# 03_ESP32.net
KiCad netlist of a schematic drawn in Altium Designer
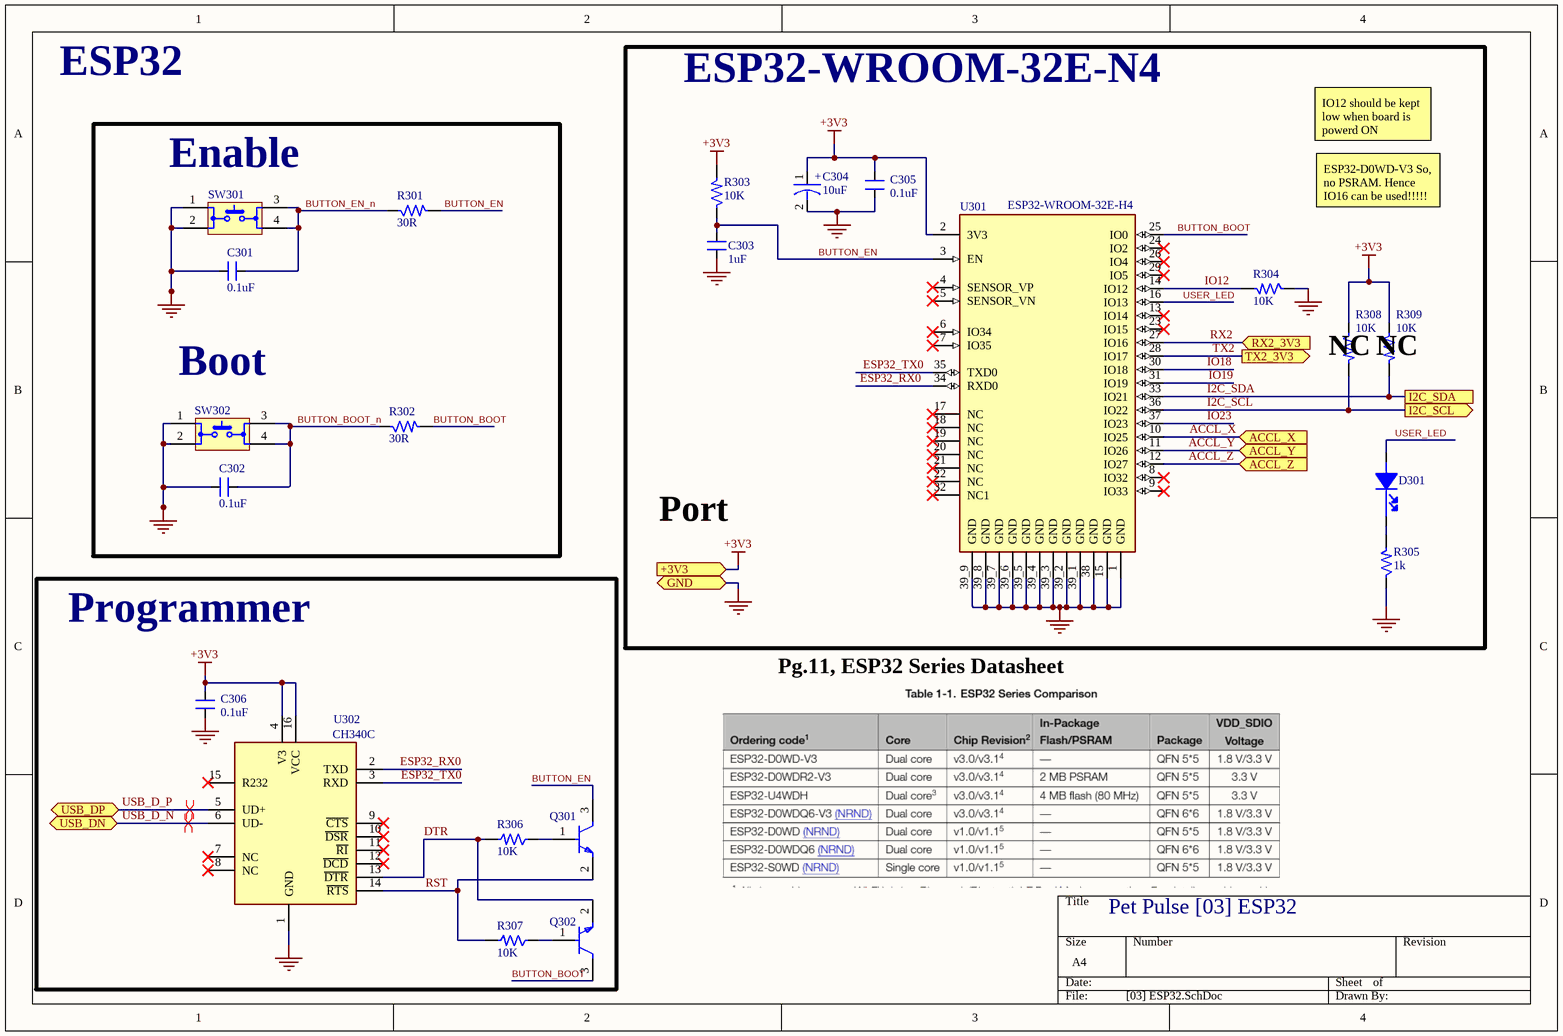
[diagram p0: [03] ESP32.SchDoc]

(export (version "E")
  (design (tool "Eeschema 10.0.6"))
  (components
    (comp (ref "C301")
      (value "0.1uF")
      (footprint "CAP_0805")
      (description "0.1µF ±10% 50V Ceramic Capacitor X7R 0805 (2012 Metric)")
      (fields
        (field (name "MANUFACTURER") "Samsung")
        (field (name "MANUFACTURER PART NUMBER") "CL21B104KBCNNNC")
      )
      (libsource (lib "IntegratedLibraryNamanTanwar") (part "CAP_0.1uF-50V-10%-0805"))
    )
    (comp (ref "C302")
      (value "0.1uF")
      (footprint "CAP_0805")
      (description "0.1µF ±10% 50V Ceramic Capacitor X7R 0805 (2012 Metric)")
      (fields
        (field (name "MANUFACTURER") "Samsung")
        (field (name "MANUFACTURER PART NUMBER") "CL21B104KBCNNNC")
      )
      (libsource (lib "IntegratedLibraryNamanTanwar") (part "CAP_0.1uF-50V-10%-0805"))
    )
    (comp (ref "C303")
      (value "1uF")
      (footprint "CAP_0805")
      (description "1µF ±5% 50V Ceramic Capacitor X7R 0805 (2012 Metric)")
      (fields
        (field (name "MANUFACTURER") "Samsung")
        (field (name "MANUFACTURER PART NUMBER") "CC0805JKX7R9BB105")
      )
      (libsource (lib "IntegratedLibraryNamanTanwar") (part "CAP_1uF-50V-5%-0805"))
    )
    (comp (ref "C304")
      (value "10uF")
      (footprint "CAP-T_1206")
      (description "10µF Molded Tantalum Capacitors 16V 1206 (3216 Metric) 3Ohm")
      (fields
        (field (name "MANUFACTURER") "AVX Corporation")
        (field (name "MANUFACTURER PART NUMBER") "TAJA106K016SNJ")
      )
      (libsource (lib "IntegratedLibraryNamanTanwar") (part "CAP-P_10uF-16V-10%-1206"))
    )
    (comp (ref "C305")
      (value "0.1uF")
      (footprint "CAP_0805")
      (description "0.1µF ±10% 50V Ceramic Capacitor X7R 0805 (2012 Metric)")
      (fields
        (field (name "MANUFACTURER") "Samsung")
        (field (name "MANUFACTURER PART NUMBER") "CL21B104KBCNNNC")
      )
      (libsource (lib "IntegratedLibraryNamanTanwar") (part "CAP_0.1uF-50V-10%-0805"))
    )
    (comp (ref "C306")
      (value "0.1uF")
      (footprint "CAP_0805")
      (description "0.1µF ±10% 50V Ceramic Capacitor X7R 0805 (2012 Metric)")
      (fields
        (field (name "MANUFACTURER") "Samsung")
        (field (name "MANUFACTURER PART NUMBER") "CL21B104KBCNNNC")
      )
      (libsource (lib "IntegratedLibraryNamanTanwar") (part "CAP_0.1uF-50V-10%-0805"))
    )
    (comp (ref "D301")
      (value "LED 0805 ORANGE")
      (footprint "LED_0805")
      (description "Orange LED 0805 Vf = 2V, 20mA")
      (fields
        (field (name "MANUFACTURER") "Osram Opto")
        (field (name "MANUFACTURER PART NUMBER") "LOR976-PS-1")
      )
      (libsource (lib "IntegratedLibraryNamanTanwar") (part "LED_ORANGE-2V-20mA- 0805"))
    )
    (comp (ref "Q301")
      (value "MMBT3904-7-F")
      (footprint "FP-SOT23-MFG")
      (description "TRANS NPN 40V 0.2A SMD SOT23-3")
      (fields (field (name "MANUFACTURER") "Diodes Incorporated"))
      (libsource (lib "IntegratedLibraryNamanTanwar") (part "TRANS_NPN_MMBT3904"))
    )
    (comp (ref "Q302")
      (value "MMBT3904-7-F")
      (footprint "FP-SOT23-MFG")
      (description "TRANS NPN 40V 0.2A SMD SOT23-3")
      (fields (field (name "MANUFACTURER") "Diodes Incorporated"))
      (libsource (lib "IntegratedLibraryNamanTanwar") (part "TRANS_NPN_MMBT3904"))
    )
    (comp (ref "R301")
      (value "30R")
      (footprint "RES_0805")
      (description "30 Ohms ±5% 0.125W, 1/8W Chip Resistor 0805 (2012 Metric) Moisture Resistant Thick Film")
      (fields
        (field (name "MANUFACTURER") "Stackpole Electronics")
        (field (name "MANUFACTURER PART NUMBER") "RC0805JR-0730RL")
      )
      (libsource (lib "IntegratedLibraryNamanTanwar") (part "RES_30R-0.125W-5%-0805"))
    )
    (comp (ref "R302")
      (value "30R")
      (footprint "RES_0805")
      (description "30 Ohms ±5% 0.125W, 1/8W Chip Resistor 0805 (2012 Metric) Moisture Resistant Thick Film")
      (fields
        (field (name "MANUFACTURER") "Stackpole Electronics")
        (field (name "MANUFACTURER PART NUMBER") "RC0805JR-0730RL")
      )
      (libsource (lib "IntegratedLibraryNamanTanwar") (part "RES_30R-0.125W-5%-0805"))
    )
    (comp (ref "R303")
      (value "10K")
      (footprint "RES_0805")
      (description "10 kOhms ±1% 0.125W, 1/8W Chip Resistor 0805 (2012 Metric) Automotive AEC-Q200 Thick Film")
      (fields (field (name "MANUFACTURER") "CTS") (field (name "MANUFACTURER PART NUMBER") "WR08X1002FTL"))
      (libsource (lib "IntegratedLibraryNamanTanwar") (part "RES_10K-0.125W-1%-0805"))
    )
    (comp (ref "R304")
      (value "10K")
      (footprint "RES_0805")
      (description "10 kOhms ±1% 0.125W, 1/8W Chip Resistor 0805 (2012 Metric) Automotive AEC-Q200 Thick Film")
      (fields (field (name "MANUFACTURER") "CTS") (field (name "MANUFACTURER PART NUMBER") "WR08X1002FTL"))
      (libsource (lib "IntegratedLibraryNamanTanwar") (part "RES_10K-0.125W-1%-0805"))
    )
    (comp (ref "R305")
      (value "1k")
      (footprint "RES_0805")
      (description "RES 1K OHM 5% 1/8W 0805")
      (fields
        (field (name "MANUFACTURER PART NUMBER") "RC0805JR-131KL")
        (field (name "MANUFACTURER") "YAGEO")
      )
      (libsource (lib "IntegratedLibraryNamanTanwar") (part "RES_1K- 0.125W-5%-0805"))
    )
    (comp (ref "R306")
      (value "10K")
      (footprint "RES_0805")
      (description "10 kOhms ±1% 0.125W, 1/8W Chip Resistor 0805 (2012 Metric) Automotive AEC-Q200 Thick Film")
      (fields (field (name "MANUFACTURER") "CTS") (field (name "MANUFACTURER PART NUMBER") "WR08X1002FTL"))
      (libsource (lib "IntegratedLibraryNamanTanwar") (part "RES_10K-0.125W-1%-0805"))
    )
    (comp (ref "R307")
      (value "10K")
      (footprint "RES_0805")
      (description "10 kOhms ±1% 0.125W, 1/8W Chip Resistor 0805 (2012 Metric) Automotive AEC-Q200 Thick Film")
      (fields (field (name "MANUFACTURER") "CTS") (field (name "MANUFACTURER PART NUMBER") "WR08X1002FTL"))
      (libsource (lib "IntegratedLibraryNamanTanwar") (part "RES_10K-0.125W-1%-0805"))
    )
    (comp (ref "R308")
      (value "10K")
      (footprint "RES_0805")
      (description "10 kOhms ±1% 0.125W, 1/8W Chip Resistor 0805 (2012 Metric) Automotive AEC-Q200 Thick Film")
      (fields (field (name "MANUFACTURER") "CTS") (field (name "MANUFACTURER PART NUMBER") "WR08X1002FTL"))
      (libsource (lib "IntegratedLibraryNamanTanwar") (part "RES_10K-0.125W-1%-0805"))
    )
    (comp (ref "R309")
      (value "10K")
      (footprint "RES_0805")
      (description "10 kOhms ±1% 0.125W, 1/8W Chip Resistor 0805 (2012 Metric) Automotive AEC-Q200 Thick Film")
      (fields (field (name "MANUFACTURER") "CTS") (field (name "MANUFACTURER PART NUMBER") "WR08X1002FTL"))
      (libsource (lib "IntegratedLibraryNamanTanwar") (part "RES_10K-0.125W-1%-0805"))
    )
    (comp (ref "SW301")
      (value "SW1_SMD_TL3305AF260QG")
      (footprint "SW_TL3305AF260QG")
      (description "Tactile Switch SPST SMD")
      (fields
        (field (name "MANUFACTURER") "E-Switch")
        (field (name "MANUFACTURER PART NUMBER") "TL3305AF260QG")
      )
      (libsource (lib "SchematicLibrary") (part "SW1_SMD_TL3305AF260QG"))
    )
    (comp (ref "SW302")
      (value "SW1_SMD_TL3305AF260QG")
      (footprint "SW_TL3305AF260QG")
      (description "Tactile Switch SPST SMD")
      (fields
        (field (name "MANUFACTURER") "E-Switch")
        (field (name "MANUFACTURER PART NUMBER") "TL3305AF260QG")
      )
      (libsource (lib "SchematicLibrary") (part "SW1_SMD_TL3305AF260QG"))
    )
    (comp (ref "U301")
      (value "ESP32-WROOM-32E-H4")
      (footprint "MOD_ESP32-WROOM-32E_(4MB_HIGH_TEMP)")
      (description "Rx Txrx Mod Wifi Trace Ant SMD")
      (fields (field (name "MANUFACTURER") "Espressif Systems"))
      (libsource (lib "IntegratedLibraryNamanTanwar") (part "MOD-ESP32-WROOM-32E-H4"))
    )
    (comp (ref "U302")
      (value "CH340C")
      (footprint "SOIC16_50_284_25X90_SMT")
      (description "USB Bridge, USB to UART USB 2.0 UART Interface")
      (fields (field (name "MANUFACTURER") "Olimex"))
      (libsource (lib "SchematicLibrary") (part "IC_CH340C"))
    )
  )
  (nets
    (net (code "1") (name "+3V3") (class "Default")
      (node (ref "C304") (pin "1") (pinfunction "1_1") (pintype "passive"))
      (node (ref "C305") (pin "2") (pinfunction "2_2") (pintype "passive"))
      (node (ref "C306") (pin "2") (pinfunction "2_2") (pintype "passive"))
      (node (ref "R303") (pin "2") (pinfunction "2_2") (pintype "passive"))
      (node (ref "R308") (pin "1") (pinfunction "1_1") (pintype "passive"))
      (node (ref "R309") (pin "1") (pinfunction "1_1") (pintype "passive"))
      (node (ref "U301") (pin "2") (pinfunction "3V3_2") (pintype "power_in"))
      (node (ref "U302") (pin "16") (pinfunction "VCC_16") (pintype "passive"))
      (node (ref "U302") (pin "4") (pinfunction "V3_4") (pintype "passive"))
    )
    (net (code "2") (name "/ACCL_X") (class "Default")
      (node (ref "U301") (pin "10") (pinfunction "IO25_10") (pintype "bidirectional"))
    )
    (net (code "3") (name "/ACCL_Y") (class "Default")
      (node (ref "U301") (pin "11") (pinfunction "IO26_11") (pintype "bidirectional"))
    )
    (net (code "4") (name "/ACCL_Z") (class "Default")
      (node (ref "U301") (pin "12") (pinfunction "IO27_12") (pintype "bidirectional"))
    )
    (net (code "5") (name "/BUTTON_BOOT") (class "Default")
      (node (ref "Q302") (pin "3") (pinfunction "C_3") (pintype "passive"))
      (node (ref "R302") (pin "2") (pinfunction "2_2") (pintype "passive"))
      (node (ref "U301") (pin "25") (pinfunction "IO0_25") (pintype "bidirectional"))
    )
    (net (code "6") (name "/BUTTON_BOOT_n") (class "Default")
      (node (ref "C302") (pin "1") (pinfunction "1_1") (pintype "passive"))
      (node (ref "R302") (pin "1") (pinfunction "1_1") (pintype "passive"))
      (node (ref "SW302") (pin "3") (pinfunction "3_3") (pintype "passive"))
      (node (ref "SW302") (pin "4") (pinfunction "4_4") (pintype "passive"))
    )
    (net (code "7") (name "/BUTTON_EN") (class "Default")
      (node (ref "C303") (pin "2") (pinfunction "2_2") (pintype "passive"))
      (node (ref "Q301") (pin "3") (pinfunction "C_3") (pintype "passive"))
      (node (ref "R301") (pin "2") (pinfunction "2_2") (pintype "passive"))
      (node (ref "R303") (pin "1") (pinfunction "1_1") (pintype "passive"))
      (node (ref "U301") (pin "3") (pinfunction "EN_3") (pintype "input"))
    )
    (net (code "8") (name "/BUTTON_EN_n") (class "Default")
      (node (ref "C301") (pin "1") (pinfunction "1_1") (pintype "passive"))
      (node (ref "R301") (pin "1") (pinfunction "1_1") (pintype "passive"))
      (node (ref "SW301") (pin "3") (pinfunction "3_3") (pintype "passive"))
      (node (ref "SW301") (pin "4") (pinfunction "4_4") (pintype "passive"))
    )
    (net (code "9") (name "/DTR") (class "Default")
      (node (ref "Q302") (pin "2") (pinfunction "E_2") (pintype "passive"))
      (node (ref "R306") (pin "2") (pinfunction "2_2") (pintype "passive"))
      (node (ref "U302") (pin "13") (pinfunction "~{DTR}_13") (pintype "passive"))
    )
    (net (code "10") (name "/ESP32_RX0") (class "Default")
      (node (ref "U301") (pin "34") (pinfunction "RXD0_34") (pintype "bidirectional"))
      (node (ref "U302") (pin "2") (pinfunction "TXD_2") (pintype "passive"))
    )
    (net (code "11") (name "/ESP32_TX0") (class "Default")
      (node (ref "U301") (pin "35") (pinfunction "TXD0_35") (pintype "bidirectional"))
      (node (ref "U302") (pin "3") (pinfunction "RXD_3") (pintype "passive"))
    )
    (net (code "12") (name "/I2C_SCL") (class "Default")
      (node (ref "R308") (pin "2") (pinfunction "2_2") (pintype "passive"))
      (node (ref "U301") (pin "36") (pinfunction "IO22_36") (pintype "bidirectional"))
    )
    (net (code "13") (name "/I2C_SDA") (class "Default")
      (node (ref "R309") (pin "2") (pinfunction "2_2") (pintype "passive"))
      (node (ref "U301") (pin "33") (pinfunction "IO21_33") (pintype "bidirectional"))
    )
    (net (code "14") (name "/IO12") (class "Default")
      (node (ref "R304") (pin "2") (pinfunction "2_2") (pintype "passive"))
      (node (ref "U301") (pin "14") (pinfunction "IO12_14") (pintype "bidirectional"))
    )
    (net (code "15") (name "/IO18") (class "Default")
      (node (ref "U301") (pin "30") (pinfunction "IO18_30") (pintype "bidirectional"))
    )
    (net (code "16") (name "/IO19") (class "Default")
      (node (ref "U301") (pin "31") (pinfunction "IO19_31") (pintype "bidirectional"))
    )
    (net (code "17") (name "/IO23") (class "Default")
      (node (ref "U301") (pin "37") (pinfunction "IO23_37") (pintype "bidirectional"))
    )
    (net (code "18") (name "/RST") (class "Default")
      (node (ref "Q301") (pin "2") (pinfunction "E_2") (pintype "passive"))
      (node (ref "R307") (pin "2") (pinfunction "2_2") (pintype "passive"))
      (node (ref "U302") (pin "14") (pinfunction "~{RTS}_14") (pintype "passive"))
    )
    (net (code "19") (name "/RX2") (class "Default")
      (node (ref "U301") (pin "27") (pinfunction "IO16_27") (pintype "bidirectional"))
    )
    (net (code "20") (name "/TX2") (class "Default")
      (node (ref "U301") (pin "28") (pinfunction "IO17_28") (pintype "bidirectional"))
    )
    (net (code "21") (name "/USB_D_N") (class "Default")
      (node (ref "U302") (pin "6") (pinfunction "UD-_6") (pintype "passive"))
    )
    (net (code "22") (name "/USB_D_P") (class "Default")
      (node (ref "U302") (pin "5") (pinfunction "UD+_5") (pintype "passive"))
    )
    (net (code "23") (name "/USER_LED") (class "Default")
      (node (ref "D301") (pin "2") (pinfunction "Anode_2") (pintype "passive"))
      (node (ref "U301") (pin "16") (pinfunction "IO13_16") (pintype "bidirectional"))
    )
    (net (code "24") (name "GND") (class "Default")
      (node (ref "C301") (pin "2") (pinfunction "2_2") (pintype "passive"))
      (node (ref "C302") (pin "2") (pinfunction "2_2") (pintype "passive"))
      (node (ref "C303") (pin "1") (pinfunction "1_1") (pintype "passive"))
      (node (ref "C304") (pin "2") (pinfunction "2_2") (pintype "passive"))
      (node (ref "C305") (pin "1") (pinfunction "1_1") (pintype "passive"))
      (node (ref "C306") (pin "1") (pinfunction "1_1") (pintype "passive"))
      (node (ref "R304") (pin "1") (pinfunction "1_1") (pintype "passive"))
      (node (ref "R305") (pin "1") (pinfunction "1_1") (pintype "passive"))
      (node (ref "SW301") (pin "1") (pinfunction "1_1") (pintype "passive"))
      (node (ref "SW301") (pin "2") (pinfunction "2_2") (pintype "passive"))
      (node (ref "SW302") (pin "1") (pinfunction "1_1") (pintype "passive"))
      (node (ref "SW302") (pin "2") (pinfunction "2_2") (pintype "passive"))
      (node (ref "U301") (pin "1") (pinfunction "GND_1") (pintype "power_in"))
      (node (ref "U301") (pin "15") (pinfunction "GND_15") (pintype "power_in"))
      (node (ref "U301") (pin "38") (pinfunction "GND_38") (pintype "power_in"))
      (node (ref "U301") (pin "39_1") (pinfunction "GND_39_1") (pintype "power_in"))
      (node (ref "U301") (pin "39_2") (pinfunction "GND_39_2") (pintype "power_in"))
      (node (ref "U301") (pin "39_3") (pinfunction "GND_39_3") (pintype "power_in"))
      (node (ref "U301") (pin "39_4") (pinfunction "GND_39_4") (pintype "power_in"))
      (node (ref "U301") (pin "39_5") (pinfunction "GND_39_5") (pintype "power_in"))
      (node (ref "U301") (pin "39_6") (pinfunction "GND_39_6") (pintype "power_in"))
      (node (ref "U301") (pin "39_7") (pinfunction "GND_39_7") (pintype "power_in"))
      (node (ref "U301") (pin "39_8") (pinfunction "GND_39_8") (pintype "power_in"))
      (node (ref "U301") (pin "39_9") (pinfunction "GND_39_9") (pintype "power_in"))
      (node (ref "U302") (pin "1") (pinfunction "GND_1") (pintype "passive"))
    )
    (net (code "25") (name "Net-(D301-Cathode)") (class "Default")
      (node (ref "D301") (pin "1") (pinfunction "Cathode_1") (pintype "passive"))
      (node (ref "R305") (pin "2") (pinfunction "2_2") (pintype "passive"))
    )
    (net (code "26") (name "Net-(Q301-B)") (class "Default")
      (node (ref "Q301") (pin "1") (pinfunction "B_1") (pintype "passive"))
      (node (ref "R306") (pin "1") (pinfunction "1_1") (pintype "passive"))
    )
    (net (code "27") (name "Net-(Q302-B)") (class "Default")
      (node (ref "Q302") (pin "1") (pinfunction "B_1") (pintype "passive"))
      (node (ref "R307") (pin "1") (pinfunction "1_1") (pintype "passive"))
    )
    (net (code "28") (name "unconnected-(U301-IO2-Pad24)") (class "Default")
      (node (ref "U301") (pin "24") (pinfunction "IO2_24") (pintype "bidirectional+no_connect"))
    )
    (net (code "29") (name "unconnected-(U301-IO4-Pad26)") (class "Default")
      (node (ref "U301") (pin "26") (pinfunction "IO4_26") (pintype "bidirectional+no_connect"))
    )
    (net (code "30") (name "unconnected-(U301-IO5-Pad29)") (class "Default")
      (node (ref "U301") (pin "29") (pinfunction "IO5_29") (pintype "bidirectional+no_connect"))
    )
    (net (code "31") (name "unconnected-(U301-IO14-Pad13)") (class "Default")
      (node (ref "U301") (pin "13") (pinfunction "IO14_13") (pintype "bidirectional+no_connect"))
    )
    (net (code "32") (name "unconnected-(U301-IO15-Pad23)") (class "Default")
      (node (ref "U301") (pin "23") (pinfunction "IO15_23") (pintype "bidirectional+no_connect"))
    )
    (net (code "33") (name "unconnected-(U301-IO32-Pad8)") (class "Default")
      (node (ref "U301") (pin "8") (pinfunction "IO32_8") (pintype "bidirectional+no_connect"))
    )
    (net (code "34") (name "unconnected-(U301-IO33-Pad9)") (class "Default")
      (node (ref "U301") (pin "9") (pinfunction "IO33_9") (pintype "bidirectional+no_connect"))
    )
    (net (code "35") (name "unconnected-(U301-IO34-Pad6)") (class "Default")
      (node (ref "U301") (pin "6") (pinfunction "IO34_6") (pintype "input+no_connect"))
    )
    (net (code "36") (name "unconnected-(U301-IO35-Pad7)") (class "Default")
      (node (ref "U301") (pin "7") (pinfunction "IO35_7") (pintype "input+no_connect"))
    )
    (net (code "37") (name "unconnected-(U301-NC-Pad17)") (class "Default")
      (node (ref "U301") (pin "17") (pinfunction "NC_17") (pintype "passive+no_connect"))
    )
    (net (code "38") (name "unconnected-(U301-NC-Pad18)") (class "Default")
      (node (ref "U301") (pin "18") (pinfunction "NC_18") (pintype "passive+no_connect"))
    )
    (net (code "39") (name "unconnected-(U301-NC-Pad19)") (class "Default")
      (node (ref "U301") (pin "19") (pinfunction "NC_19") (pintype "passive+no_connect"))
    )
    (net (code "40") (name "unconnected-(U301-NC-Pad20)") (class "Default")
      (node (ref "U301") (pin "20") (pinfunction "NC_20") (pintype "passive+no_connect"))
    )
    (net (code "41") (name "unconnected-(U301-NC-Pad21)") (class "Default")
      (node (ref "U301") (pin "21") (pinfunction "NC_21") (pintype "passive+no_connect"))
    )
    (net (code "42") (name "unconnected-(U301-NC-Pad22)") (class "Default")
      (node (ref "U301") (pin "22") (pinfunction "NC_22") (pintype "passive+no_connect"))
    )
    (net (code "43") (name "unconnected-(U301-NC1-Pad32)") (class "Default")
      (node (ref "U301") (pin "32") (pinfunction "NC1_32") (pintype "passive+no_connect"))
    )
    (net (code "44") (name "unconnected-(U301-SENSOR_VN-Pad5)") (class "Default")
      (node (ref "U301") (pin "5") (pinfunction "SENSOR_VN_5") (pintype "input+no_connect"))
    )
    (net (code "45") (name "unconnected-(U301-SENSOR_VP-Pad4)") (class "Default")
      (node (ref "U301") (pin "4") (pinfunction "SENSOR_VP_4") (pintype "input+no_connect"))
    )
    (net (code "46") (name "unconnected-(U302-NC-Pad7)") (class "Default")
      (node (ref "U302") (pin "7") (pinfunction "NC_7") (pintype "passive+no_connect"))
    )
    (net (code "47") (name "unconnected-(U302-NC-Pad8)") (class "Default")
      (node (ref "U302") (pin "8") (pinfunction "NC_8") (pintype "passive+no_connect"))
    )
    (net (code "48") (name "unconnected-(U302-R232-Pad15)") (class "Default")
      (node (ref "U302") (pin "15") (pinfunction "R232_15") (pintype "passive+no_connect"))
    )
    (net (code "49") (name "unconnected-(U302-~{CTS}-Pad9)") (class "Default")
      (node (ref "U302") (pin "9") (pinfunction "~{CTS}_9") (pintype "passive+no_connect"))
    )
    (net (code "50") (name "unconnected-(U302-~{DCD}-Pad12)") (class "Default")
      (node (ref "U302") (pin "12") (pinfunction "~{DCD}_12") (pintype "passive+no_connect"))
    )
    (net (code "51") (name "unconnected-(U302-~{DSR}-Pad10)") (class "Default")
      (node (ref "U302") (pin "10") (pinfunction "~{DSR}_10") (pintype "passive+no_connect"))
    )
    (net (code "52") (name "unconnected-(U302-~{RI}-Pad11)") (class "Default")
      (node (ref "U302") (pin "11") (pinfunction "~{RI}_11") (pintype "passive+no_connect"))
    )
  )
)
